# 7segment.net
KiCad netlist of a schematic drawn in Altium Designer
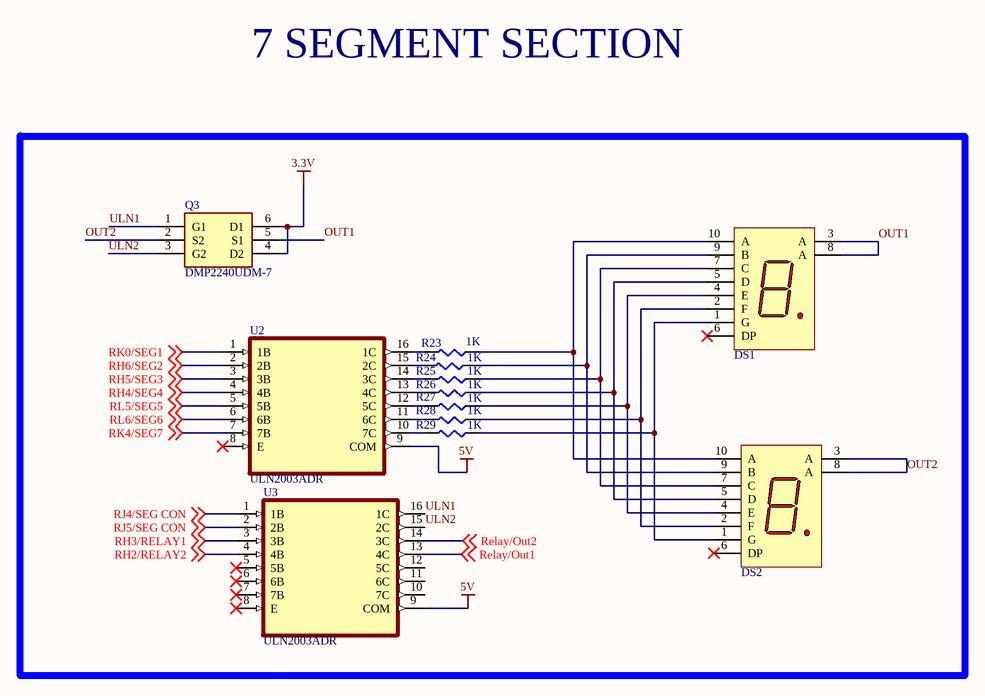
[diagram p0: 7segment.SchDoc]

(export (version "E")
  (design (tool "Eeschema 10.0.6"))
  (components
    (comp (ref "DS1")
      (value "157119S12801")
      (footprint "WL-T7DS_L13W10H7")
      (description "WL-T7DS 7 Segments Display THT Single Digit, 0.39\"/ 9.9mm, Common Anode, 38mcd, 2V, Super Red")
      (fields (field (name "MANUFACTURER") "Wurth Elektronik"))
      (libsource (lib "wruth 7 segment") (part "157119S12801"))
    )
    (comp (ref "DS2")
      (value "157119S12801")
      (footprint "WL-T7DS_L13W10H7")
      (description "WL-T7DS 7 Segments Display THT Single Digit, 0.39\"/ 9.9mm, Common Anode, 38mcd, 2V, Super Red")
      (fields (field (name "MANUFACTURER") "Wurth Elektronik"))
      (libsource (lib "wruth 7 segment") (part "157119S12801"))
    )
    (comp (ref "Q3")
      (value "DMP2240UDM-7")
      (footprint "SamacSys:SOT95P285X140-6N")
      (description "MOSFET (P-Channel)")
      (fields (field (name "MOUSER PART NUMBER") "621-DMP2240UDM-7"))
      (libsource (lib "*") (part "DMP2240UDM-7"))
    )
    (comp (ref "R23")
      (value "1K")
      (footprint "SMD-0805-RES")
      (description "RES SMD 1K OHM 1% 1/8W 0805")
      (fields
        (field (name "PART NUMBER") "ERJ-6ENF1001V")
        (field (name "DIGI-KEY PART NUMBER") "P1.00KCCT-ND")
      )
      (libsource (lib "Panasonic_ERJ_0805") (part "ERJ-6ENF1001V"))
    )
    (comp (ref "R24")
      (value "1K")
      (footprint "SMD-0805-RES")
      (description "RES SMD 1K OHM 1% 1/8W 0805")
      (fields
        (field (name "PART NUMBER") "ERJ-6ENF1001V")
        (field (name "DIGI-KEY PART NUMBER") "P1.00KCCT-ND")
      )
      (libsource (lib "Panasonic_ERJ_0805") (part "ERJ-6ENF1001V"))
    )
    (comp (ref "R25")
      (value "1K")
      (footprint "SMD-0805-RES")
      (description "RES SMD 1K OHM 1% 1/8W 0805")
      (fields
        (field (name "PART NUMBER") "ERJ-6ENF1001V")
        (field (name "DIGI-KEY PART NUMBER") "P1.00KCCT-ND")
      )
      (libsource (lib "Panasonic_ERJ_0805") (part "ERJ-6ENF1001V"))
    )
    (comp (ref "R26")
      (value "1K")
      (footprint "SMD-0805-RES")
      (description "RES SMD 1K OHM 1% 1/8W 0805")
      (fields
        (field (name "PART NUMBER") "ERJ-6ENF1001V")
        (field (name "DIGI-KEY PART NUMBER") "P1.00KCCT-ND")
      )
      (libsource (lib "Panasonic_ERJ_0805") (part "ERJ-6ENF1001V"))
    )
    (comp (ref "R27")
      (value "1K")
      (footprint "SMD-0805-RES")
      (description "RES SMD 1K OHM 1% 1/8W 0805")
      (fields
        (field (name "PART NUMBER") "ERJ-6ENF1001V")
        (field (name "DIGI-KEY PART NUMBER") "P1.00KCCT-ND")
      )
      (libsource (lib "Panasonic_ERJ_0805") (part "ERJ-6ENF1001V"))
    )
    (comp (ref "R28")
      (value "1K")
      (footprint "SMD-0805-RES")
      (description "RES SMD 1K OHM 1% 1/8W 0805")
      (fields
        (field (name "PART NUMBER") "ERJ-6ENF1001V")
        (field (name "DIGI-KEY PART NUMBER") "P1.00KCCT-ND")
      )
      (libsource (lib "Panasonic_ERJ_0805") (part "ERJ-6ENF1001V"))
    )
    (comp (ref "R29")
      (value "1K")
      (footprint "SMD-0805-RES")
      (description "RES SMD 1K OHM 1% 1/8W 0805")
      (fields
        (field (name "PART NUMBER") "ERJ-6ENF1001V")
        (field (name "DIGI-KEY PART NUMBER") "P1.00KCCT-ND")
      )
      (libsource (lib "Panasonic_ERJ_0805") (part "ERJ-6ENF1001V"))
    )
    (comp (ref "U2")
      (value "ULN2003ADR")
      (footprint "SOIC127P600X175-16N")
      (description "50-V, 7-ch darlington transistor array, -20C to 70C")
      (fields (field (name "MF") "Texas Instruments"))
      (libsource (lib "ULN2003ADR") (part "ULN2003ADR"))
    )
    (comp (ref "U3")
      (value "ULN2003ADR")
      (footprint "SOIC127P600X175-16N")
      (description "50-V, 7-ch darlington transistor array, -20C to 70C")
      (fields (field (name "MF") "Texas Instruments"))
      (libsource (lib "ULN2003ADR") (part "ULN2003ADR"))
    )
  )
  (nets
    (net (code "1") (name "/OUT1") (class "Default")
      (node (ref "DS1") (pin "3") (pinfunction "A_3") (pintype "passive"))
      (node (ref "DS1") (pin "8") (pinfunction "A_8") (pintype "passive"))
      (node (ref "Q3") (pin "5") (pinfunction "S1_5") (pintype "passive"))
    )
    (net (code "2") (name "/OUT2") (class "Default")
      (node (ref "DS2") (pin "3") (pinfunction "A_3") (pintype "passive"))
      (node (ref "DS2") (pin "8") (pinfunction "A_8") (pintype "passive"))
      (node (ref "Q3") (pin "2") (pinfunction "S2_2") (pintype "passive"))
    )
    (net (code "3") (name "/ULN1") (class "Default")
      (node (ref "Q3") (pin "1") (pinfunction "G1_1") (pintype "passive"))
      (node (ref "U3") (pin "16") (pinfunction "1C_16") (pintype "output"))
    )
    (net (code "4") (name "/ULN2") (class "Default")
      (node (ref "Q3") (pin "3") (pinfunction "G2_3") (pintype "passive"))
      (node (ref "U3") (pin "15") (pinfunction "2C_15") (pintype "output"))
    )
    (net (code "5") (name "3.3V") (class "Default")
      (node (ref "Q3") (pin "4") (pinfunction "D2_4") (pintype "passive"))
      (node (ref "Q3") (pin "6") (pinfunction "D1_6") (pintype "passive"))
    )
    (net (code "6") (name "5V") (class "Default")
      (node (ref "U2") (pin "9") (pinfunction "COM_9") (pintype "output"))
      (node (ref "U3") (pin "9") (pinfunction "COM_9") (pintype "output"))
    )
    (net (code "7") (name "Net-(DS1-A-Pad10)") (class "Default")
      (node (ref "DS1") (pin "10") (pinfunction "A_10") (pintype "passive"))
      (node (ref "DS2") (pin "10") (pinfunction "A_10") (pintype "passive"))
      (node (ref "R23") (pin "1") (pinfunction "1_1") (pintype "passive"))
    )
    (net (code "8") (name "Net-(DS1-B)") (class "Default")
      (node (ref "DS1") (pin "9") (pinfunction "B_9") (pintype "passive"))
      (node (ref "DS2") (pin "9") (pinfunction "B_9") (pintype "passive"))
      (node (ref "R24") (pin "1") (pinfunction "1_1") (pintype "passive"))
    )
    (net (code "9") (name "Net-(DS1-C)") (class "Default")
      (node (ref "DS1") (pin "7") (pinfunction "C_7") (pintype "passive"))
      (node (ref "DS2") (pin "7") (pinfunction "C_7") (pintype "passive"))
      (node (ref "R25") (pin "1") (pinfunction "1_1") (pintype "passive"))
    )
    (net (code "10") (name "Net-(DS1-D)") (class "Default")
      (node (ref "DS1") (pin "5") (pinfunction "D_5") (pintype "passive"))
      (node (ref "DS2") (pin "5") (pinfunction "D_5") (pintype "passive"))
      (node (ref "R26") (pin "1") (pinfunction "1_1") (pintype "passive"))
    )
    (net (code "11") (name "Net-(DS1-E)") (class "Default")
      (node (ref "DS1") (pin "4") (pinfunction "E_4") (pintype "passive"))
      (node (ref "DS2") (pin "4") (pinfunction "E_4") (pintype "passive"))
      (node (ref "R27") (pin "1") (pinfunction "1_1") (pintype "passive"))
    )
    (net (code "12") (name "Net-(DS1-F)") (class "Default")
      (node (ref "DS1") (pin "2") (pinfunction "F_2") (pintype "passive"))
      (node (ref "DS2") (pin "2") (pinfunction "F_2") (pintype "passive"))
      (node (ref "R28") (pin "1") (pinfunction "1_1") (pintype "passive"))
    )
    (net (code "13") (name "Net-(DS1-G)") (class "Default")
      (node (ref "DS1") (pin "1") (pinfunction "G_1") (pintype "passive"))
      (node (ref "DS2") (pin "1") (pinfunction "G_1") (pintype "passive"))
      (node (ref "R29") (pin "1") (pinfunction "1_1") (pintype "passive"))
    )
    (net (code "14") (name "Net-(U2-1C)") (class "Default")
      (node (ref "R23") (pin "2") (pinfunction "2_2") (pintype "passive"))
      (node (ref "U2") (pin "16") (pinfunction "1C_16") (pintype "output"))
    )
    (net (code "15") (name "Net-(U2-2C)") (class "Default")
      (node (ref "R24") (pin "2") (pinfunction "2_2") (pintype "passive"))
      (node (ref "U2") (pin "15") (pinfunction "2C_15") (pintype "output"))
    )
    (net (code "16") (name "Net-(U2-3C)") (class "Default")
      (node (ref "R25") (pin "2") (pinfunction "2_2") (pintype "passive"))
      (node (ref "U2") (pin "14") (pinfunction "3C_14") (pintype "output"))
    )
    (net (code "17") (name "Net-(U2-4C)") (class "Default")
      (node (ref "R26") (pin "2") (pinfunction "2_2") (pintype "passive"))
      (node (ref "U2") (pin "13") (pinfunction "4C_13") (pintype "output"))
    )
    (net (code "18") (name "Net-(U2-5C)") (class "Default")
      (node (ref "R27") (pin "2") (pinfunction "2_2") (pintype "passive"))
      (node (ref "U2") (pin "12") (pinfunction "5C_12") (pintype "output"))
    )
    (net (code "19") (name "Net-(U2-6C)") (class "Default")
      (node (ref "R28") (pin "2") (pinfunction "2_2") (pintype "passive"))
      (node (ref "U2") (pin "11") (pinfunction "6C_11") (pintype "output"))
    )
    (net (code "20") (name "Net-(U2-7C)") (class "Default")
      (node (ref "R29") (pin "2") (pinfunction "2_2") (pintype "passive"))
      (node (ref "U2") (pin "10") (pinfunction "7C_10") (pintype "output"))
    )
    (net (code "21") (name "RH2{slash}RELAY2") (class "Default")
      (node (ref "U3") (pin "4") (pinfunction "4B_4") (pintype "input"))
    )
    (net (code "22") (name "RH3{slash}RELAY1") (class "Default")
      (node (ref "U3") (pin "3") (pinfunction "3B_3") (pintype "input"))
    )
    (net (code "23") (name "RH4{slash}SEG4") (class "Default")
      (node (ref "U2") (pin "4") (pinfunction "4B_4") (pintype "input"))
    )
    (net (code "24") (name "RH5{slash}SEG3") (class "Default")
      (node (ref "U2") (pin "3") (pinfunction "3B_3") (pintype "input"))
    )
    (net (code "25") (name "RH6{slash}SEG2") (class "Default")
      (node (ref "U2") (pin "2") (pinfunction "2B_2") (pintype "input"))
    )
    (net (code "26") (name "RJ4{slash}SEG CON") (class "Default")
      (node (ref "U3") (pin "1") (pinfunction "1B_1") (pintype "input"))
    )
    (net (code "27") (name "RJ5{slash}SEG CON") (class "Default")
      (node (ref "U3") (pin "2") (pinfunction "2B_2") (pintype "input"))
    )
    (net (code "28") (name "RK0{slash}SEG1") (class "Default")
      (node (ref "U2") (pin "1") (pinfunction "1B_1") (pintype "input"))
    )
    (net (code "29") (name "RK4{slash}SEG7") (class "Default")
      (node (ref "U2") (pin "7") (pinfunction "7B_7") (pintype "input"))
    )
    (net (code "30") (name "RL5{slash}SEG5") (class "Default")
      (node (ref "U2") (pin "5") (pinfunction "5B_5") (pintype "input"))
    )
    (net (code "31") (name "RL6{slash}SEG6") (class "Default")
      (node (ref "U2") (pin "6") (pinfunction "6B_6") (pintype "input"))
    )
    (net (code "32") (name "Relay{slash}Out1") (class "Default")
      (node (ref "U3") (pin "13") (pinfunction "4C_13") (pintype "output"))
    )
    (net (code "33") (name "Relay{slash}Out2") (class "Default")
      (node (ref "U3") (pin "14") (pinfunction "3C_14") (pintype "output"))
    )
    (net (code "34") (name "unconnected-(DS1-DP-Pad6)") (class "Default")
      (node (ref "DS1") (pin "6") (pinfunction "DP_6") (pintype "passive+no_connect"))
    )
    (net (code "35") (name "unconnected-(DS2-DP-Pad6)") (class "Default")
      (node (ref "DS2") (pin "6") (pinfunction "DP_6") (pintype "passive+no_connect"))
    )
    (net (code "36") (name "unconnected-(U2-E-Pad8)") (class "Default")
      (node (ref "U2") (pin "8") (pinfunction "E_8") (pintype "input+no_connect"))
    )
    (net (code "37") (name "unconnected-(U3-5B-Pad5)") (class "Default")
      (node (ref "U3") (pin "5") (pinfunction "5B_5") (pintype "input+no_connect"))
    )
    (net (code "38") (name "unconnected-(U3-5C-Pad12)") (class "Default")
      (node (ref "U3") (pin "12") (pinfunction "5C_12") (pintype "output"))
    )
    (net (code "39") (name "unconnected-(U3-6B-Pad6)") (class "Default")
      (node (ref "U3") (pin "6") (pinfunction "6B_6") (pintype "input+no_connect"))
    )
    (net (code "40") (name "unconnected-(U3-6C-Pad11)") (class "Default")
      (node (ref "U3") (pin "11") (pinfunction "6C_11") (pintype "output"))
    )
    (net (code "41") (name "unconnected-(U3-7B-Pad7)") (class "Default")
      (node (ref "U3") (pin "7") (pinfunction "7B_7") (pintype "input+no_connect"))
    )
    (net (code "42") (name "unconnected-(U3-7C-Pad10)") (class "Default")
      (node (ref "U3") (pin "10") (pinfunction "7C_10") (pintype "output"))
    )
    (net (code "43") (name "unconnected-(U3-E-Pad8)") (class "Default")
      (node (ref "U3") (pin "8") (pinfunction "E_8") (pintype "input+no_connect"))
    )
  )
)
